# micro.net
KiCad netlist of a schematic drawn in Altium Designer
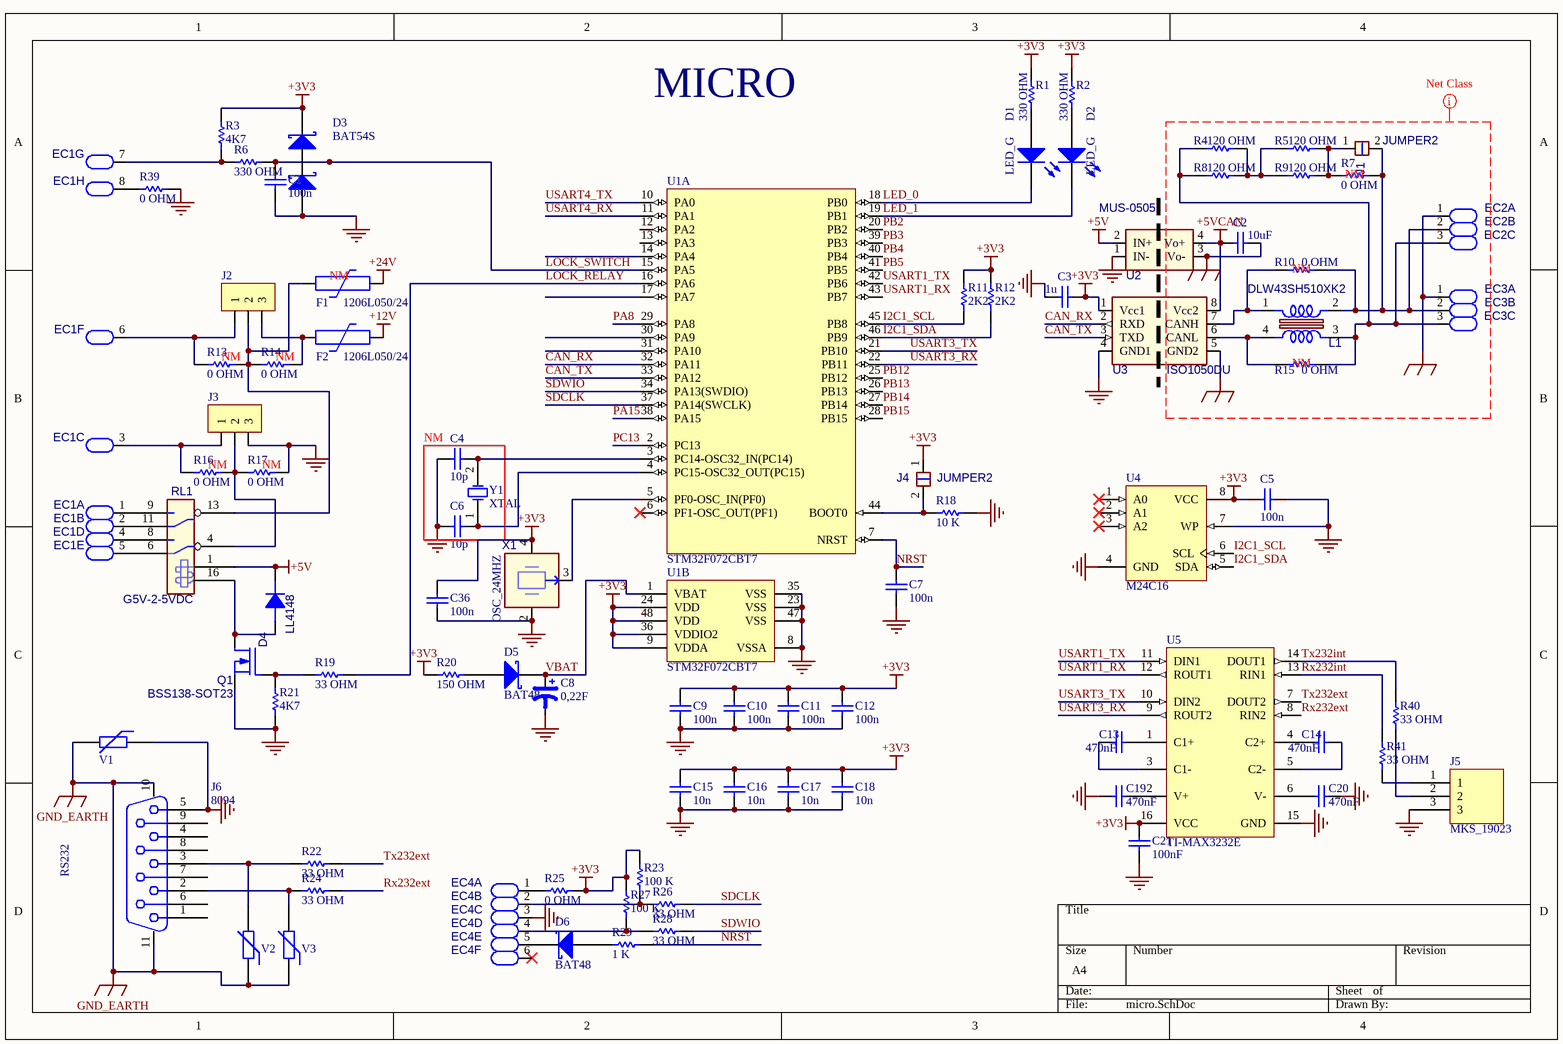
[diagram p0: micro.SchDoc]

(export (version "E")
  (design (tool "Eeschema 10.0.6"))
  (components
    (comp (ref "C1")
      (value "100n")
      (footprint "0603")
      (description "Capacitor")
      (fields (field (name "PUBLISHER") "Altium Limited"))
      (libsource (lib "sallen") (part "cond"))
    )
    (comp (ref "C2")
      (value "10uF")
      (footprint "0805")
      (description "Capacitor")
      (fields (field (name "PUBLISHER") "Altium Limited"))
      (libsource (lib "sallen") (part "cond"))
    )
    (comp (ref "C3")
      (value "1u")
      (footprint "0603")
      (description "Capacitor")
      (fields (field (name "PUBLISHER") "Altium Limited"))
      (libsource (lib "sallen") (part "cond"))
    )
    (comp (ref "C4")
      (value "10p")
      (footprint "0603")
      (description "Capacitor")
      (fields (field (name "PUBLISHER") "Altium Limited"))
      (libsource (lib "sallen") (part "cond"))
    )
    (comp (ref "C5")
      (value "100n")
      (footprint "0603")
      (description "Capacitor")
      (fields (field (name "PUBLISHER") "Altium Limited"))
      (libsource (lib "sallen") (part "cond"))
    )
    (comp (ref "C6")
      (value "10p")
      (footprint "0603")
      (description "Capacitor")
      (fields (field (name "PUBLISHER") "Altium Limited"))
      (libsource (lib "sallen") (part "cond"))
    )
    (comp (ref "C7")
      (value "100n")
      (footprint "0603")
      (description "Capacitor")
      (fields (field (name "PUBLISHER") "Altium Limited"))
      (libsource (lib "sallen") (part "cond"))
    )
    (comp (ref "C8")
      (value "0,22F")
      (footprint "EECRG0V224V")
      (description "Polarized Capacitor (Axial)")
      (fields (field (name "PUBLISHER") "Altium Limited"))
      (libsource (lib "sallen") (part "cond_pol_super"))
    )
    (comp (ref "C9")
      (value "100n")
      (footprint "0603")
      (description "Capacitor")
      (fields (field (name "PUBLISHER") "Altium Limited"))
      (libsource (lib "sallen") (part "cond"))
    )
    (comp (ref "C10")
      (value "100n")
      (footprint "0603")
      (description "Capacitor")
      (fields (field (name "PUBLISHER") "Altium Limited"))
      (libsource (lib "sallen") (part "cond"))
    )
    (comp (ref "C11")
      (value "100n")
      (footprint "0603")
      (description "Capacitor")
      (fields (field (name "PUBLISHER") "Altium Limited"))
      (libsource (lib "sallen") (part "cond"))
    )
    (comp (ref "C12")
      (value "100n")
      (footprint "0603")
      (description "Capacitor")
      (fields (field (name "PUBLISHER") "Altium Limited"))
      (libsource (lib "sallen") (part "cond"))
    )
    (comp (ref "C13")
      (value "470nF")
      (footprint "0805")
      (description "Capacitor")
      (fields (field (name "PUBLISHER") "Altium Limited"))
      (libsource (lib "sallen") (part "cond"))
    )
    (comp (ref "C14")
      (value "470nF")
      (footprint "0805")
      (description "Capacitor")
      (fields (field (name "PUBLISHER") "Altium Limited"))
      (libsource (lib "sallen") (part "cond"))
    )
    (comp (ref "C15")
      (value "10n")
      (footprint "0603")
      (description "Capacitor")
      (fields (field (name "PUBLISHER") "Altium Limited"))
      (libsource (lib "sallen") (part "cond"))
    )
    (comp (ref "C16")
      (value "10n")
      (footprint "0603")
      (description "Capacitor")
      (fields (field (name "PUBLISHER") "Altium Limited"))
      (libsource (lib "sallen") (part "cond"))
    )
    (comp (ref "C17")
      (value "10n")
      (footprint "0603")
      (description "Capacitor")
      (fields (field (name "PUBLISHER") "Altium Limited"))
      (libsource (lib "sallen") (part "cond"))
    )
    (comp (ref "C18")
      (value "10n")
      (footprint "0603")
      (description "Capacitor")
      (fields (field (name "PUBLISHER") "Altium Limited"))
      (libsource (lib "sallen") (part "cond"))
    )
    (comp (ref "C19")
      (value "470nF")
      (footprint "0805")
      (description "Capacitor")
      (fields (field (name "PUBLISHER") "Altium Limited"))
      (libsource (lib "sallen") (part "cond"))
    )
    (comp (ref "C20")
      (value "470nF")
      (footprint "0805")
      (description "Capacitor")
      (fields (field (name "PUBLISHER") "Altium Limited"))
      (libsource (lib "sallen") (part "cond"))
    )
    (comp (ref "C21")
      (value "100nF")
      (footprint "0805")
      (description "Capacitor")
      (fields (field (name "PUBLISHER") "Altium Limited"))
      (libsource (lib "sallen") (part "cond"))
    )
    (comp (ref "C36")
      (value "100n")
      (footprint "0603")
      (description "Capacitor")
      (fields (field (name "PUBLISHER") "Altium Limited"))
      (libsource (lib "sallen") (part "cond"))
    )
    (comp (ref "D1")
      (value "LED_G")
      (footprint "LED0603G")
      (description "Typical RED, GREEN, YELLOW, AMBER GaAs LED")
      (fields (field (name "PUBLISHER") "Altium Limited"))
      (libsource (lib "sallen") (part "diodo_led"))
    )
    (comp (ref "D2")
      (value "LED_G")
      (footprint "LED0603G")
      (description "Typical RED, GREEN, YELLOW, AMBER GaAs LED")
      (fields (field (name "PUBLISHER") "Altium Limited"))
      (libsource (lib "sallen") (part "diodo_led"))
    )
    (comp (ref "D3")
      (value "BAT54S")
      (footprint "SOT23")
      (description "High Current Density Surface Mount Schottky Rectifier")
      (libsource (lib "sallen") (part "BAT54S"))
    )
    (comp (ref "D4")
      (value "LL4148")
      (description "DIODE SWITCH,100V,150MA,SOD123")
      (libsource (lib "LMB_Board") (part "LL4148_(06006001)"))
    )
    (comp (ref "D5")
      (value "BAT48")
      (footprint "0805")
      (description "Schottky Diode")
      (fields (field (name "PUBLISHER") "Altium Limited"))
      (libsource (lib "sallen") (part "D Schottky"))
    )
    (comp (ref "D6")
      (value "BAT48")
      (footprint "0805")
      (description "Schottky Diode")
      (fields (field (name "PUBLISHER") "Altium Limited"))
      (libsource (lib "sallen") (part "D Schottky"))
    )
    (comp (ref "EC1")
      (value "JST_XAD_8")
      (description "Conector 8(2x4) vias (3A)")
      (libsource (lib "LMB_Board") (part "Conn_JST_XADSS_8_vias"))
    )
    (comp (ref "EC2")
      (value "Conexcon-2545-2-03-1_1")
      (description "2.54mm pitch Terminal Block 3P")
      (fields (field (name "PART NUMBER") "Conexcon-2545-2-03-1"))
      (libsource (lib "sallen") (part "Conexcon-2545-2-03-1_1"))
    )
    (comp (ref "EC3")
      (value "Conexcon-2545-2-03-1_1")
      (description "2.54mm pitch Terminal Block 3P")
      (fields (field (name "PART NUMBER") "Conexcon-2545-2-03-1"))
      (libsource (lib "sallen") (part "Conexcon-2545-2-03-1_1"))
    )
    (comp (ref "EC4")
      (value "Conexcon-2545-2-06-1")
      (description "2.54mm pitch Terminal Block 6P")
      (libsource (lib "sallen") (part "Conexcon-2545-2-06-1"))
    )
    (comp (ref "F1")
      (value "1206L050/24")
      (footprint "POLYFUSE_1206L")
      (libsource (lib "dpm_semiconductores") (part "POLYFUSE_1206L050/24"))
    )
    (comp (ref "F2")
      (value "1206L050/24")
      (footprint "POLYFUSE_1206L")
      (libsource (lib "dpm_semiconductores") (part "POLYFUSE_1206L050/24"))
    )
    (comp (ref "J1")
      (value "JUMPER2")
      (description "Jumper 2pin P=2.54mm")
      (libsource (lib "") (part "JUMPER2_1"))
    )
    (comp (ref "J2")
      (value "Header 3")
      (footprint "HDR1X3")
      (description "Header, 3-Pin")
      (fields (field (name "PUBLISHER") "Altium Limited"))
      (libsource (lib "sallen") (part "Header 3"))
    )
    (comp (ref "J3")
      (value "Header 3")
      (footprint "HDR1X3")
      (description "Header, 3-Pin")
      (fields (field (name "PUBLISHER") "Altium Limited"))
      (libsource (lib "sallen") (part "Header 3"))
    )
    (comp (ref "J4")
      (value "JUMPER2")
      (description "Jumper 2pin P=2.54mm")
      (libsource (lib "sallen") (part "JUMPER2"))
    )
    (comp (ref "J5")
      (value "MKS_19023")
      (footprint "MOLEX_MKS_19023")
      (description "Molex_MKS_19023")
      (libsource (lib "sallen") (part "MOLEX_MKS_19023"))
    )
    (comp (ref "J6") (value "8094") (footprint "8094") (libsource (lib "dpm_conectores") (part "8094")))
    (comp (ref "L1")
      (value "DLW43SH510XK2")
      (footprint "1812_DLW")
      (description "Bobina Common mode 51uH 230mA 1.0Ohm SMD 1812 /Murata")
      (libsource (lib "sallen") (part "DLW43SH510XK2"))
    )
    (comp (ref "Q1")
      (value "BSS138-SOT23")
      (description "N-Channel Logic Level Enhancement Mode Field Effect Transistor")
      (libsource (lib "LMB_Board") (part "BSS138-SOT23"))
    )
    (comp (ref "R1")
      (value "330 OHM")
      (footprint "R0603")
      (description "Resistor")
      (fields (field (name "PUBLISHER") "Altium Limited"))
      (libsource (lib "sallen") (part "res1"))
    )
    (comp (ref "R2")
      (value "330 OHM")
      (footprint "R0603")
      (description "Resistor")
      (fields (field (name "PUBLISHER") "Altium Limited"))
      (libsource (lib "sallen") (part "res1"))
    )
    (comp (ref "R3")
      (value "4K7")
      (footprint "R0603")
      (description "Resistor")
      (fields (field (name "PUBLISHER") "Altium Limited"))
      (libsource (lib "sallen") (part "res1"))
    )
    (comp (ref "R4")
      (value "120 OHM")
      (footprint "R0603")
      (description "Resistor")
      (fields (field (name "PUBLISHER") "Altium Limited"))
      (libsource (lib "sallen") (part "res1"))
    )
    (comp (ref "R5")
      (value "120 OHM")
      (footprint "R0603")
      (description "Resistor")
      (fields (field (name "PUBLISHER") "Altium Limited"))
      (libsource (lib "sallen") (part "res1"))
    )
    (comp (ref "R6")
      (value "330 OHM")
      (footprint "R0603")
      (description "Resistor")
      (fields (field (name "PUBLISHER") "Altium Limited"))
      (libsource (lib "sallen") (part "res1"))
    )
    (comp (ref "R7")
      (value "0 OHM")
      (footprint "R0603")
      (description "Resistor")
      (fields (field (name "PUBLISHER") "Altium Limited"))
      (libsource (lib "sallen") (part "res1"))
    )
    (comp (ref "R8")
      (value "120 OHM")
      (footprint "R0603")
      (description "Resistor")
      (fields (field (name "PUBLISHER") "Altium Limited"))
      (libsource (lib "sallen") (part "res1"))
    )
    (comp (ref "R9")
      (value "120 OHM")
      (footprint "R0603")
      (description "Resistor")
      (fields (field (name "PUBLISHER") "Altium Limited"))
      (libsource (lib "sallen") (part "res1"))
    )
    (comp (ref "R10")
      (value "0 OHM")
      (footprint "R0603")
      (description "Resistor")
      (fields (field (name "PUBLISHER") "Altium Limited"))
      (libsource (lib "sallen") (part "res1"))
    )
    (comp (ref "R11")
      (value "2K2")
      (footprint "R0603")
      (description "Resistor")
      (fields (field (name "PUBLISHER") "Altium Limited"))
      (libsource (lib "sallen") (part "res1"))
    )
    (comp (ref "R12")
      (value "2K2")
      (footprint "R0603")
      (description "Resistor")
      (fields (field (name "PUBLISHER") "Altium Limited"))
      (libsource (lib "sallen") (part "res1"))
    )
    (comp (ref "R13")
      (value "0 OHM")
      (footprint "R0805")
      (description "Resistor")
      (fields (field (name "PUBLISHER") "Altium Limited"))
      (libsource (lib "sallen") (part "res1"))
    )
    (comp (ref "R14")
      (value "0 OHM")
      (footprint "R0805")
      (description "Resistor")
      (fields (field (name "PUBLISHER") "Altium Limited"))
      (libsource (lib "sallen") (part "res1"))
    )
    (comp (ref "R15")
      (value "0 OHM")
      (footprint "R0603")
      (description "Resistor")
      (fields (field (name "PUBLISHER") "Altium Limited"))
      (libsource (lib "sallen") (part "res1"))
    )
    (comp (ref "R16")
      (value "0 OHM")
      (footprint "R0805")
      (description "Resistor")
      (fields (field (name "PUBLISHER") "Altium Limited"))
      (libsource (lib "sallen") (part "res1"))
    )
    (comp (ref "R17")
      (value "0 OHM")
      (footprint "R0805")
      (description "Resistor")
      (fields (field (name "PUBLISHER") "Altium Limited"))
      (libsource (lib "sallen") (part "res1"))
    )
    (comp (ref "R18")
      (value "10 K")
      (footprint "R0603")
      (description "Resistor")
      (fields (field (name "PUBLISHER") "Altium Limited"))
      (libsource (lib "sallen") (part "res1"))
    )
    (comp (ref "R19")
      (value "33 OHM")
      (footprint "R0603")
      (description "Resistor")
      (fields (field (name "PUBLISHER") "Altium Limited"))
      (libsource (lib "sallen") (part "res1"))
    )
    (comp (ref "R20")
      (value "150 OHM")
      (footprint "R0603")
      (description "Resistor")
      (fields (field (name "PUBLISHER") "Altium Limited"))
      (libsource (lib "sallen") (part "res1"))
    )
    (comp (ref "R21")
      (value "4K7")
      (footprint "R0603")
      (description "Resistor")
      (fields (field (name "PUBLISHER") "Altium Limited"))
      (libsource (lib "sallen") (part "res1"))
    )
    (comp (ref "R22")
      (value "33 OHM")
      (footprint "R0603")
      (description "Resistor")
      (fields (field (name "PUBLISHER") "Altium Limited"))
      (libsource (lib "sallen") (part "res1"))
    )
    (comp (ref "R23")
      (value "100 K")
      (footprint "R0603")
      (description "Resistor")
      (fields (field (name "PUBLISHER") "Altium Limited"))
      (libsource (lib "sallen") (part "res1"))
    )
    (comp (ref "R24")
      (value "33 OHM")
      (footprint "R0603")
      (description "Resistor")
      (fields (field (name "PUBLISHER") "Altium Limited"))
      (libsource (lib "sallen") (part "res1"))
    )
    (comp (ref "R25")
      (value "0 OHM")
      (footprint "R0603")
      (description "Resistor")
      (fields (field (name "PUBLISHER") "Altium Limited"))
      (libsource (lib "sallen") (part "res1"))
    )
    (comp (ref "R26")
      (value "33 OHM")
      (footprint "R0603")
      (description "Resistor")
      (fields (field (name "PUBLISHER") "Altium Limited"))
      (libsource (lib "sallen") (part "res1"))
    )
    (comp (ref "R27")
      (value "100 K")
      (footprint "R0603")
      (description "Resistor")
      (fields (field (name "PUBLISHER") "Altium Limited"))
      (libsource (lib "sallen") (part "res1"))
    )
    (comp (ref "R28")
      (value "33 OHM")
      (footprint "R0603")
      (description "Resistor")
      (fields (field (name "PUBLISHER") "Altium Limited"))
      (libsource (lib "sallen") (part "res1"))
    )
    (comp (ref "R29")
      (value "1 K")
      (footprint "R0603")
      (description "Resistor")
      (fields (field (name "PUBLISHER") "Altium Limited"))
      (libsource (lib "sallen") (part "res1"))
    )
    (comp (ref "R39")
      (value "0 OHM")
      (footprint "R0603")
      (description "Resistor")
      (fields (field (name "PUBLISHER") "Altium Limited"))
      (libsource (lib "sallen") (part "res1"))
    )
    (comp (ref "R40")
      (value "33 OHM")
      (footprint "R0603")
      (description "Resistor")
      (fields (field (name "PUBLISHER") "Altium Limited"))
      (libsource (lib "sallen") (part "res1"))
    )
    (comp (ref "R41")
      (value "33 OHM")
      (footprint "R0603")
      (description "Resistor")
      (fields (field (name "PUBLISHER") "Altium Limited"))
      (libsource (lib "sallen") (part "res1"))
    )
    (comp (ref "RL1")
      (value "G5V-2-5VDC")
      (footprint "RL-OMRON-G5V-2-5VDC")
      (description "Omrom Relay G5V-2-5VDC")
      (libsource (lib "LMB_Board") (part "G5V-2-5VDC"))
    )
    (comp (ref "U1")
      (value "STM32F072CBT7")
      (footprint "STM-LQFP48_N_3d")
      (libsource (lib "sallen") (part "STM32F072CBT7"))
    )
    (comp (ref "U2")
      (value "MUS-0505")
      (description "Convertidor DC/DC isolated 1W 5v/5v 1.8E DANUBE (eQ XpPower IE0505S)")
      (libsource (lib "sallen") (part "MUS-0505"))
    )
    (comp (ref "U3")
      (value "ISO1050DU")
      (description "CAN Transceiver Isolated 3-5vcc (-55º-105ºC)SOP8-DIP")
      (libsource (lib "sallen") (part "ISO1050DU"))
    )
    (comp (ref "U4")
      (value "M24C16")
      (footprint "SO08")
      (libsource (lib "sallen") (part "MEM-SEEPROM-AT24C-IL8"))
    )
    (comp (ref "U5")
      (value "TI-MAX3232E")
      (footprint "SOIC16")
      (libsource (lib "sallen") (part "TI-MAX3232E"))
    )
    (comp (ref "V1")
      (value "VC080526C580")
      (footprint "VC080526C580")
      (description "Varistor (Voltage-Sensitive Resistor)")
      (libsource (lib "dpm_pasivos") (part "VC080526C580"))
    )
    (comp (ref "V2")
      (value "VC080526C580")
      (footprint "VC080526C580")
      (description "Varistor (Voltage-Sensitive Resistor)")
      (libsource (lib "dpm_pasivos") (part "VC080526C580"))
    )
    (comp (ref "V3")
      (value "VC080526C580")
      (footprint "VC080526C580")
      (description "Varistor (Voltage-Sensitive Resistor)")
      (libsource (lib "dpm_pasivos") (part "VC080526C580"))
    )
    (comp (ref "X1")
      (value "OSC_24MHZ")
      (description "Oscillator 7x5mm 24Mhz 3.3v 4p s73305T-24 //Aker-usa")
      (libsource (lib "LMB_Board") (part "OSC7X5_4P3.3-24MHZ"))
    )
    (comp (ref "Y1")
      (value "XTAL")
      (footprint "R38")
      (description "Crystal Oscillator")
      (fields (field (name "PUBLISHER") "Altium Limited"))
      (libsource (lib "Miscellaneous Devices") (part "XTAL"))
    )
  )
  (nets
    (net (code "1") (name "+3V3") (class "Default")
      (node (ref "C10") (pin "2") (pinfunction "2_2") (pintype "passive"))
      (node (ref "C11") (pin "2") (pinfunction "2_2") (pintype "passive"))
      (node (ref "C12") (pin "2") (pinfunction "2_2") (pintype "passive"))
      (node (ref "C15") (pin "2") (pinfunction "2_2") (pintype "passive"))
      (node (ref "C16") (pin "2") (pinfunction "2_2") (pintype "passive"))
      (node (ref "C17") (pin "2") (pinfunction "2_2") (pintype "passive"))
      (node (ref "C18") (pin "2") (pinfunction "2_2") (pintype "passive"))
      (node (ref "C21") (pin "1") (pinfunction "1_1") (pintype "passive"))
      (node (ref "C3") (pin "1") (pinfunction "1_1") (pintype "passive"))
      (node (ref "C36") (pin "2") (pinfunction "2_2") (pintype "passive"))
      (node (ref "C5") (pin "2") (pinfunction "2_2") (pintype "passive"))
      (node (ref "C9") (pin "2") (pinfunction "2_2") (pintype "passive"))
      (node (ref "D3") (pin "2") (pinfunction "K_2") (pintype "passive"))
      (node (ref "J4") (pin "1") (pinfunction "1_1") (pintype "passive"))
      (node (ref "R1") (pin "2") (pinfunction "2_2") (pintype "passive"))
      (node (ref "R11") (pin "1") (pinfunction "1_1") (pintype "passive"))
      (node (ref "R12") (pin "1") (pinfunction "1_1") (pintype "passive"))
      (node (ref "R2") (pin "2") (pinfunction "2_2") (pintype "passive"))
      (node (ref "R20") (pin "1") (pinfunction "1_1") (pintype "passive"))
      (node (ref "R23") (pin "2") (pinfunction "2_2") (pintype "passive"))
      (node (ref "R25") (pin "1") (pinfunction "1_1") (pintype "passive"))
      (node (ref "R27") (pin "2") (pinfunction "2_2") (pintype "passive"))
      (node (ref "R3") (pin "2") (pinfunction "2_2") (pintype "passive"))
      (node (ref "U1") (pin "24") (pinfunction "VDD_24") (pintype "power_in"))
      (node (ref "U1") (pin "36") (pinfunction "VDDIO2_36") (pintype "power_in"))
      (node (ref "U1") (pin "48") (pinfunction "VDD_48") (pintype "power_in"))
      (node (ref "U1") (pin "9") (pinfunction "VDDA_9") (pintype "power_in"))
      (node (ref "U3") (pin "1") (pinfunction "Vcc1_1") (pintype "power_in"))
      (node (ref "U4") (pin "8") (pinfunction "VCC_8") (pintype "power_in"))
      (node (ref "U5") (pin "16") (pinfunction "VCC_16") (pintype "power_in"))
      (node (ref "X1") (pin "4") (pinfunction "4_4") (pintype "passive"))
    )
    (net (code "2") (name "+5V") (class "Default")
      (node (ref "D4") (pin "2") (pinfunction "K_2") (pintype "passive"))
      (node (ref "RL1") (pin "1") (pinfunction "COIL1_1") (pintype "passive"))
      (node (ref "U2") (pin "2") (pinfunction "IN+_2") (pintype "power_in"))
    )
    (net (code "3") (name "+5VCAN") (class "Default")
      (node (ref "C2") (pin "1") (pinfunction "1_1") (pintype "passive"))
      (node (ref "U2") (pin "4") (pinfunction "Vo+_4") (pintype "power_in"))
      (node (ref "U3") (pin "8") (pinfunction "Vcc2_8") (pintype "power_in"))
    )
    (net (code "4") (name "+12V") (class "Default")
      (node (ref "F2") (pin "2") (pinfunction "2_2") (pintype "passive"))
    )
    (net (code "5") (name "+24V") (class "Default")
      (node (ref "F1") (pin "2") (pinfunction "2_2") (pintype "passive"))
    )
    (net (code "6") (name "/CAN_RX") (class "Default")
      (node (ref "U1") (pin "32") (pinfunction "PA11_32") (pintype "bidirectional"))
      (node (ref "U3") (pin "2") (pinfunction "RXD_2") (pintype "output"))
    )
    (net (code "7") (name "/CAN_TX") (class "Default")
      (node (ref "U1") (pin "33") (pinfunction "PA12_33") (pintype "bidirectional"))
      (node (ref "U3") (pin "3") (pinfunction "TXD_3") (pintype "input"))
    )
    (net (code "8") (name "/I2C1_SCL") (class "Default")
      (node (ref "R11") (pin "2") (pinfunction "2_2") (pintype "passive"))
      (node (ref "U1") (pin "45") (pinfunction "PB8_45") (pintype "bidirectional"))
      (node (ref "U4") (pin "6") (pinfunction "SCL_6") (pintype "input"))
    )
    (net (code "9") (name "/I2C1_SDA") (class "Default")
      (node (ref "R12") (pin "2") (pinfunction "2_2") (pintype "passive"))
      (node (ref "U1") (pin "46") (pinfunction "PB9_46") (pintype "bidirectional"))
      (node (ref "U4") (pin "5") (pinfunction "SDA_5") (pintype "bidirectional"))
    )
    (net (code "10") (name "/LED_0") (class "Default")
      (node (ref "D1") (pin "2") (pinfunction "K_2") (pintype "passive"))
      (node (ref "U1") (pin "18") (pinfunction "PB0_18") (pintype "bidirectional"))
    )
    (net (code "11") (name "/LED_1") (class "Default")
      (node (ref "D2") (pin "2") (pinfunction "K_2") (pintype "passive"))
      (node (ref "U1") (pin "19") (pinfunction "PB1_19") (pintype "bidirectional"))
    )
    (net (code "12") (name "/LOCK_RELAY") (class "Default")
      (node (ref "R19") (pin "2") (pinfunction "2_2") (pintype "passive"))
      (node (ref "U1") (pin "16") (pinfunction "PA6_16") (pintype "bidirectional"))
    )
    (net (code "13") (name "/LOCK_SWITCH") (class "Default")
      (node (ref "C1") (pin "2") (pinfunction "2_2") (pintype "passive"))
      (node (ref "D3") (pin "3") (pinfunction "KA_3") (pintype "passive"))
      (node (ref "R6") (pin "1") (pinfunction "1_1") (pintype "passive"))
      (node (ref "U1") (pin "15") (pinfunction "PA5_15") (pintype "bidirectional"))
    )
    (net (code "14") (name "/NRST") (class "Default")
      (node (ref "C7") (pin "2") (pinfunction "2_2") (pintype "passive"))
      (node (ref "R29") (pin "2") (pinfunction "2_2") (pintype "passive"))
      (node (ref "U1") (pin "7") (pinfunction "NRST_7") (pintype "bidirectional"))
    )
    (net (code "15") (name "/PA8") (class "Default")
      (node (ref "U1") (pin "29") (pinfunction "PA8_29") (pintype "bidirectional"))
    )
    (net (code "16") (name "/PA15") (class "Default")
      (node (ref "U1") (pin "38") (pinfunction "PA15_38") (pintype "bidirectional"))
    )
    (net (code "17") (name "/PB2") (class "Default")
      (node (ref "U1") (pin "20") (pinfunction "PB2_20") (pintype "bidirectional"))
    )
    (net (code "18") (name "/PB3") (class "Default")
      (node (ref "U1") (pin "39") (pinfunction "PB3_39") (pintype "bidirectional"))
    )
    (net (code "19") (name "/PB4") (class "Default")
      (node (ref "U1") (pin "40") (pinfunction "PB4_40") (pintype "bidirectional"))
    )
    (net (code "20") (name "/PB5") (class "Default")
      (node (ref "U1") (pin "41") (pinfunction "PB5_41") (pintype "bidirectional"))
    )
    (net (code "21") (name "/PB12") (class "Default")
      (node (ref "U1") (pin "25") (pinfunction "PB12_25") (pintype "bidirectional"))
    )
    (net (code "22") (name "/PB13") (class "Default")
      (node (ref "U1") (pin "26") (pinfunction "PB13_26") (pintype "bidirectional"))
    )
    (net (code "23") (name "/PB14") (class "Default")
      (node (ref "U1") (pin "27") (pinfunction "PB14_27") (pintype "bidirectional"))
    )
    (net (code "24") (name "/PB15") (class "Default")
      (node (ref "U1") (pin "28") (pinfunction "PB15_28") (pintype "bidirectional"))
    )
    (net (code "25") (name "/PC13") (class "Default")
      (node (ref "U1") (pin "2") (pinfunction "PC13_2") (pintype "bidirectional"))
    )
    (net (code "26") (name "/Rx232ext") (class "Default")
      (node (ref "R24") (pin "2") (pinfunction "2_2") (pintype "passive"))
      (node (ref "U5") (pin "8") (pinfunction "RIN2_8") (pintype "input"))
    )
    (net (code "27") (name "/Rx232int") (class "Default")
      (node (ref "R41") (pin "2") (pinfunction "2_2") (pintype "passive"))
      (node (ref "U5") (pin "13") (pinfunction "RIN1_13") (pintype "input"))
    )
    (net (code "28") (name "/SDCLK") (class "Default")
      (node (ref "R26") (pin "2") (pinfunction "2_2") (pintype "passive"))
      (node (ref "U1") (pin "37") (pinfunction "PA14(SWCLK)_37") (pintype "bidirectional"))
    )
    (net (code "29") (name "/SDWIO") (class "Default")
      (node (ref "R28") (pin "2") (pinfunction "2_2") (pintype "passive"))
      (node (ref "U1") (pin "34") (pinfunction "PA13(SWDIO)_34") (pintype "bidirectional"))
    )
    (net (code "30") (name "/Tx232ext") (class "Default")
      (node (ref "R22") (pin "2") (pinfunction "2_2") (pintype "passive"))
      (node (ref "U5") (pin "7") (pinfunction "DOUT2_7") (pintype "output"))
    )
    (net (code "31") (name "/Tx232int") (class "Default")
      (node (ref "R40") (pin "2") (pinfunction "2_2") (pintype "passive"))
      (node (ref "U5") (pin "14") (pinfunction "DOUT1_14") (pintype "output"))
    )
    (net (code "32") (name "/USART1_RX") (class "Default")
      (node (ref "U1") (pin "43") (pinfunction "PB7_43") (pintype "bidirectional"))
      (node (ref "U5") (pin "12") (pinfunction "ROUT1_12") (pintype "output"))
    )
    (net (code "33") (name "/USART1_TX") (class "Default")
      (node (ref "U1") (pin "42") (pinfunction "PB6_42") (pintype "bidirectional"))
      (node (ref "U5") (pin "11") (pinfunction "DIN1_11") (pintype "input"))
    )
    (net (code "34") (name "/USART3_RX") (class "Default")
      (node (ref "U1") (pin "22") (pinfunction "PB11_22") (pintype "bidirectional"))
      (node (ref "U5") (pin "9") (pinfunction "ROUT2_9") (pintype "output"))
    )
    (net (code "35") (name "/USART3_TX") (class "Default")
      (node (ref "U1") (pin "21") (pinfunction "PB10_21") (pintype "bidirectional"))
      (node (ref "U5") (pin "10") (pinfunction "DIN2_10") (pintype "input"))
    )
    (net (code "36") (name "/USART4_RX") (class "Default")
      (node (ref "U1") (pin "11") (pinfunction "PA1_11") (pintype "bidirectional"))
    )
    (net (code "37") (name "/USART4_TX") (class "Default")
      (node (ref "U1") (pin "10") (pinfunction "PA0_10") (pintype "bidirectional"))
    )
    (net (code "38") (name "/VBAT") (class "Default")
      (node (ref "C8") (pin "1") (pinfunction "1_1") (pintype "passive"))
      (node (ref "D5") (pin "2") (pinfunction "K_2") (pintype "passive"))
      (node (ref "U1") (pin "1") (pinfunction "VBAT_1") (pintype "power_in"))
    )
    (net (code "39") (name "GND") (class "Default")
      (node (ref "C1") (pin "1") (pinfunction "1_1") (pintype "passive"))
      (node (ref "C10") (pin "1") (pinfunction "1_1") (pintype "passive"))
      (node (ref "C11") (pin "1") (pinfunction "1_1") (pintype "passive"))
      (node (ref "C12") (pin "1") (pinfunction "1_1") (pintype "passive"))
      (node (ref "C15") (pin "1") (pinfunction "1_1") (pintype "passive"))
      (node (ref "C16") (pin "1") (pinfunction "1_1") (pintype "passive"))
      (node (ref "C17") (pin "1") (pinfunction "1_1") (pintype "passive"))
      (node (ref "C18") (pin "1") (pinfunction "1_1") (pintype "passive"))
      (node (ref "C19") (pin "1") (pinfunction "1_1") (pintype "passive"))
      (node (ref "C20") (pin "2") (pinfunction "2_2") (pintype "passive"))
      (node (ref "C21") (pin "2") (pinfunction "2_2") (pintype "passive"))
      (node (ref "C3") (pin "2") (pinfunction "2_2") (pintype "passive"))
      (node (ref "C36") (pin "1") (pinfunction "1_1") (pintype "passive"))
      (node (ref "C4") (pin "1") (pinfunction "1_1") (pintype "passive"))
      (node (ref "C5") (pin "1") (pinfunction "1_1") (pintype "passive"))
      (node (ref "C6") (pin "1") (pinfunction "1_1") (pintype "passive"))
      (node (ref "C7") (pin "1") (pinfunction "1_1") (pintype "passive"))
      (node (ref "C8") (pin "2") (pinfunction "2_2") (pintype "passive"))
      (node (ref "C9") (pin "1") (pinfunction "1_1") (pintype "passive"))
      (node (ref "D3") (pin "1") (pinfunction "A_1") (pintype "passive"))
      (node (ref "EC4") (pin "3") (pinfunction "3_3") (pintype "passive"))
      (node (ref "J3") (pin "3") (pinfunction "3_3") (pintype "passive"))
      (node (ref "J5") (pin "3") (pinfunction "3_3") (pintype "passive"))
      (node (ref "J6") (pin "5") (pinfunction "5_5") (pintype "passive"))
      (node (ref "Q1") (pin "S") (pinfunction "S_S") (pintype "passive"))
      (node (ref "R17") (pin "1") (pinfunction "1_1") (pintype "passive"))
      (node (ref "R18") (pin "1") (pinfunction "1_1") (pintype "passive"))
      (node (ref "R21") (pin "1") (pinfunction "1_1") (pintype "passive"))
      (node (ref "R39") (pin "1") (pinfunction "1_1") (pintype "passive"))
      (node (ref "U1") (pin "23") (pinfunction "VSS_23") (pintype "power_in"))
      (node (ref "U1") (pin "35") (pinfunction "VSS_35") (pintype "power_in"))
      (node (ref "U1") (pin "47") (pinfunction "VSS_47") (pintype "power_in"))
      (node (ref "U1") (pin "8") (pinfunction "VSSA_8") (pintype "power_in"))
      (node (ref "U2") (pin "1") (pinfunction "IN-_1") (pintype "power_in"))
      (node (ref "U3") (pin "4") (pinfunction "GND1_4") (pintype "power_in"))
      (node (ref "U4") (pin "4") (pinfunction "GND_4") (pintype "power_in"))
      (node (ref "U4") (pin "7") (pinfunction "WP_7") (pintype "input"))
      (node (ref "U5") (pin "15") (pinfunction "GND_15") (pintype "power_in"))
      (node (ref "V1") (pin "1") (pinfunction "1_1") (pintype "passive"))
      (node (ref "X1") (pin "2") (pinfunction "2_2") (pintype "passive"))
    )
    (net (code "40") (name "GND_CAN") (class "Default")
      (node (ref "C2") (pin "2") (pinfunction "2_2") (pintype "passive"))
      (node (ref "EC2") (pin "1") (pinfunction "1_1") (pintype "passive"))
      (node (ref "EC3") (pin "1") (pinfunction "1_1") (pintype "passive"))
      (node (ref "U2") (pin "3") (pinfunction "Vo-_3") (pintype "power_in"))
      (node (ref "U3") (pin "5") (pinfunction "GND2_5") (pintype "power_in"))
    )
    (net (code "41") (name "GND_EARTH") (class "Default")
      (node (ref "J6") (pin "10") (pinfunction "10_10") (pintype "passive"))
      (node (ref "J6") (pin "11") (pinfunction "11_11") (pintype "passive"))
      (node (ref "V1") (pin "2") (pinfunction "2_2") (pintype "passive"))
      (node (ref "V2") (pin "1") (pinfunction "1_1") (pintype "passive"))
      (node (ref "V3") (pin "1") (pinfunction "1_1") (pintype "passive"))
    )
    (net (code "42") (name "Net-(D1-A)") (class "Default")
      (node (ref "D1") (pin "1") (pinfunction "A_1") (pintype "passive"))
      (node (ref "R1") (pin "1") (pinfunction "1_1") (pintype "passive"))
    )
    (net (code "43") (name "Net-(D2-A)") (class "Default")
      (node (ref "D2") (pin "1") (pinfunction "A_1") (pintype "passive"))
      (node (ref "R2") (pin "1") (pinfunction "1_1") (pintype "passive"))
    )
    (net (code "44") (name "Net-(D4-A)") (class "Default")
      (node (ref "D4") (pin "1") (pinfunction "A_1") (pintype "passive"))
      (node (ref "Q1") (pin "D") (pinfunction "D_D") (pintype "passive"))
      (node (ref "RL1") (pin "16") (pinfunction "COIL2_16") (pintype "passive"))
    )
    (net (code "45") (name "Net-(D5-A)") (class "Default")
      (node (ref "D5") (pin "1") (pinfunction "A_1") (pintype "passive"))
      (node (ref "R20") (pin "2") (pinfunction "2_2") (pintype "passive"))
    )
    (net (code "46") (name "Net-(D6-A)") (class "Default")
      (node (ref "D6") (pin "1") (pinfunction "A_1") (pintype "passive"))
      (node (ref "R29") (pin "1") (pinfunction "1_1") (pintype "passive"))
    )
    (net (code "47") (name "Net-(D6-K)") (class "Default")
      (node (ref "D6") (pin "2") (pinfunction "K_2") (pintype "passive"))
      (node (ref "EC4") (pin "5") (pinfunction "5_5") (pintype "passive"))
    )
    (net (code "48") (name "Net-(EC1-Pad1)") (class "Default")
      (node (ref "EC1") (pin "1") (pinfunction "1_1") (pintype "passive"))
      (node (ref "RL1") (pin "9") (pinfunction "NO_9") (pintype "passive"))
    )
    (net (code "49") (name "Net-(EC1-Pad2)") (class "Default")
      (node (ref "EC1") (pin "2") (pinfunction "2_2") (pintype "passive"))
      (node (ref "RL1") (pin "11") (pinfunction "NO_11") (pintype "passive"))
    )
    (net (code "50") (name "Net-(EC1-Pad3)") (class "Default")
      (node (ref "EC1") (pin "3") (pinfunction "3_3") (pintype "passive"))
      (node (ref "J3") (pin "1") (pinfunction "1_1") (pintype "passive"))
      (node (ref "R16") (pin "2") (pinfunction "2_2") (pintype "passive"))
    )
    (net (code "51") (name "Net-(EC1-Pad4)") (class "Default")
      (node (ref "EC1") (pin "4") (pinfunction "4_4") (pintype "passive"))
      (node (ref "RL1") (pin "8") (pinfunction "NO_8") (pintype "passive"))
    )
    (net (code "52") (name "Net-(EC1-Pad5)") (class "Default")
      (node (ref "EC1") (pin "5") (pinfunction "5_5") (pintype "passive"))
      (node (ref "RL1") (pin "6") (pinfunction "NO_6") (pintype "passive"))
    )
    (net (code "53") (name "Net-(EC1-Pad6)") (class "Default")
      (node (ref "EC1") (pin "6") (pinfunction "6_6") (pintype "passive"))
      (node (ref "J2") (pin "1") (pinfunction "1_1") (pintype "passive"))
      (node (ref "R13") (pin "2") (pinfunction "2_2") (pintype "passive"))
    )
    (net (code "54") (name "Net-(EC1-Pad7)") (class "Default")
      (node (ref "EC1") (pin "7") (pinfunction "7_7") (pintype "passive"))
      (node (ref "R3") (pin "1") (pinfunction "1_1") (pintype "passive"))
      (node (ref "R6") (pin "2") (pinfunction "2_2") (pintype "passive"))
    )
    (net (code "55") (name "Net-(EC1-Pad8)") (class "Default")
      (node (ref "EC1") (pin "8") (pinfunction "8_8") (pintype "passive"))
      (node (ref "R39") (pin "2") (pinfunction "2_2") (pintype "passive"))
    )
    (net (code "56") (name "Net-(EC2-Pad2)") (class "Default")
      (node (ref "EC2") (pin "2") (pinfunction "2_2") (pintype "passive"))
      (node (ref "EC3") (pin "2") (pinfunction "2_2") (pintype "passive"))
      (node (ref "J1") (pin "2") (pinfunction "2_2") (pintype "passive"))
      (node (ref "L1") (pin "2") (pinfunction "2_2") (pintype "passive"))
      (node (ref "R10") (pin "2") (pinfunction "2_2") (pintype "passive"))
      (node (ref "R7") (pin "2") (pinfunction "2_2") (pintype "passive"))
    )
    (net (code "57") (name "Net-(EC2-Pad3)") (class "Default")
      (node (ref "EC2") (pin "3") (pinfunction "3_3") (pintype "passive"))
      (node (ref "EC3") (pin "3") (pinfunction "3_3") (pintype "passive"))
      (node (ref "L1") (pin "3") (pinfunction "3_3") (pintype "passive"))
      (node (ref "R15") (pin "2") (pinfunction "2_2") (pintype "passive"))
      (node (ref "R4") (pin "1") (pinfunction "1_1") (pintype "passive"))
      (node (ref "R8") (pin "1") (pinfunction "1_1") (pintype "passive"))
    )
    (net (code "58") (name "Net-(EC4-Pad1)") (class "Default")
      (node (ref "EC4") (pin "1") (pinfunction "1_1") (pintype "passive"))
      (node (ref "R25") (pin "2") (pinfunction "2_2") (pintype "passive"))
    )
    (net (code "59") (name "Net-(EC4-Pad2)") (class "Default")
      (node (ref "EC4") (pin "2") (pinfunction "2_2") (pintype "passive"))
      (node (ref "R23") (pin "1") (pinfunction "1_1") (pintype "passive"))
      (node (ref "R26") (pin "1") (pinfunction "1_1") (pintype "passive"))
    )
    (net (code "60") (name "Net-(EC4-Pad4)") (class "Default")
      (node (ref "EC4") (pin "4") (pinfunction "4_4") (pintype "passive"))
      (node (ref "R27") (pin "1") (pinfunction "1_1") (pintype "passive"))
      (node (ref "R28") (pin "1") (pinfunction "1_1") (pintype "passive"))
    )
    (net (code "61") (name "Net-(F1-Pad1)") (class "Default")
      (node (ref "F1") (pin "1") (pinfunction "1_1") (pintype "passive"))
      (node (ref "J2") (pin "2") (pinfunction "2_2") (pintype "passive"))
      (node (ref "R13") (pin "1") (pinfunction "1_1") (pintype "passive"))
      (node (ref "R14") (pin "2") (pinfunction "2_2") (pintype "passive"))
      (node (ref "RL1") (pin "13") (pinfunction "COMMON_13") (pintype "passive"))
    )
    (net (code "62") (name "Net-(F2-Pad1)") (class "Default")
      (node (ref "F2") (pin "1") (pinfunction "1_1") (pintype "passive"))
      (node (ref "J2") (pin "3") (pinfunction "3_3") (pintype "passive"))
      (node (ref "R14") (pin "1") (pinfunction "1_1") (pintype "passive"))
    )
    (net (code "63") (name "Net-(J1-Pad1)") (class "Default")
      (node (ref "J1") (pin "1") (pinfunction "1_1") (pintype "passive"))
      (node (ref "R5") (pin "2") (pinfunction "2_2") (pintype "passive"))
      (node (ref "R7") (pin "1") (pinfunction "1_1") (pintype "passive"))
      (node (ref "R9") (pin "2") (pinfunction "2_2") (pintype "passive"))
    )
    (net (code "64") (name "Net-(J3-Pad2)") (class "Default")
      (node (ref "J3") (pin "2") (pinfunction "2_2") (pintype "passive"))
      (node (ref "R16") (pin "1") (pinfunction "1_1") (pintype "passive"))
      (node (ref "R17") (pin "2") (pinfunction "2_2") (pintype "passive"))
      (node (ref "RL1") (pin "4") (pinfunction "COMMON_4") (pintype "passive"))
    )
    (net (code "65") (name "Net-(J5-Pad1)") (class "Default")
      (node (ref "J5") (pin "1") (pinfunction "1_1") (pintype "passive"))
      (node (ref "R41") (pin "1") (pinfunction "1_1") (pintype "passive"))
    )
    (net (code "66") (name "Net-(J5-Pad2)") (class "Default")
      (node (ref "J5") (pin "2") (pinfunction "2_2") (pintype "passive"))
      (node (ref "R40") (pin "1") (pinfunction "1_1") (pintype "passive"))
    )
    (net (code "67") (name "Net-(J6-Pad2)") (class "Default")
      (node (ref "J6") (pin "2") (pinfunction "2_2") (pintype "passive"))
      (node (ref "R24") (pin "1") (pinfunction "1_1") (pintype "passive"))
      (node (ref "V3") (pin "2") (pinfunction "2_2") (pintype "passive"))
    )
    (net (code "68") (name "Net-(J6-Pad3)") (class "Default")
      (node (ref "J6") (pin "3") (pinfunction "3_3") (pintype "passive"))
      (node (ref "R22") (pin "1") (pinfunction "1_1") (pintype "passive"))
      (node (ref "V2") (pin "2") (pinfunction "2_2") (pintype "passive"))
    )
    (net (code "69") (name "Net-(Q1-PadG)") (class "Default")
      (node (ref "Q1") (pin "G") (pinfunction "G_G") (pintype "passive"))
      (node (ref "R19") (pin "1") (pinfunction "1_1") (pintype "passive"))
      (node (ref "R21") (pin "2") (pinfunction "2_2") (pintype "passive"))
    )
    (net (code "70") (name "Net-(R4-Pad2)") (class "Default")
      (node (ref "R4") (pin "2") (pinfunction "2_2") (pintype "passive"))
      (node (ref "R5") (pin "1") (pinfunction "1_1") (pintype "passive"))
      (node (ref "R8") (pin "2") (pinfunction "2_2") (pintype "passive"))
      (node (ref "R9") (pin "1") (pinfunction "1_1") (pintype "passive"))
    )
    (net (code "71") (name "Net-(U1A-BOOT0)") (class "Default")
      (node (ref "J4") (pin "2") (pinfunction "2_2") (pintype "passive"))
      (node (ref "R18") (pin "2") (pinfunction "2_2") (pintype "passive"))
      (node (ref "U1") (pin "44") (pinfunction "BOOT0_44") (pintype "input"))
    )
    (net (code "72") (name "Net-(U1A-PC14-OSC32_IN(PC14))") (class "Default")
      (node (ref "C4") (pin "2") (pinfunction "2_2") (pintype "passive"))
      (node (ref "U1") (pin "3") (pinfunction "PC14-OSC32_IN(PC14)_3") (pintype "bidirectional"))
      (node (ref "Y1") (pin "2") (pinfunction "OSC2_2") (pintype "passive"))
    )
    (net (code "73") (name "Net-(U1A-PC15-OSC32_OUT(PC15))") (class "Default")
      (node (ref "C6") (pin "2") (pinfunction "2_2") (pintype "passive"))
      (node (ref "U1") (pin "4") (pinfunction "PC15-OSC32_OUT(PC15)_4") (pintype "bidirectional"))
      (node (ref "Y1") (pin "1") (pinfunction "OSC1_1") (pintype "passive"))
    )
    (net (code "74") (name "Net-(U1A-PF0-OSC_IN(PF0))") (class "Default")
      (node (ref "U1") (pin "5") (pinfunction "PF0-OSC_IN(PF0)_5") (pintype "bidirectional"))
      (node (ref "X1") (pin "3") (pinfunction "3_3") (pintype "passive"))
    )
    (net (code "75") (name "Net-(U3-CANH)") (class "Default")
      (node (ref "L1") (pin "1") (pinfunction "1_1") (pintype "passive"))
      (node (ref "R10") (pin "1") (pinfunction "1_1") (pintype "passive"))
      (node (ref "U3") (pin "7") (pinfunction "CANH_7") (pintype "bidirectional"))
    )
    (net (code "76") (name "Net-(U3-CANL)") (class "Default")
      (node (ref "L1") (pin "4") (pinfunction "4_4") (pintype "passive"))
      (node (ref "R15") (pin "1") (pinfunction "1_1") (pintype "passive"))
      (node (ref "U3") (pin "6") (pinfunction "CANL_6") (pintype "bidirectional"))
    )
    (net (code "77") (name "Net-(U5-C1+)") (class "Default")
      (node (ref "C13") (pin "2") (pinfunction "2_2") (pintype "passive"))
      (node (ref "U5") (pin "1") (pinfunction "C1+_1") (pintype "passive"))
    )
    (net (code "78") (name "Net-(U5-C1-)") (class "Default")
      (node (ref "C13") (pin "1") (pinfunction "1_1") (pintype "passive"))
      (node (ref "U5") (pin "3") (pinfunction "C1-_3") (pintype "passive"))
    )
    (net (code "79") (name "Net-(U5-C2+)") (class "Default")
      (node (ref "C14") (pin "1") (pinfunction "1_1") (pintype "passive"))
      (node (ref "U5") (pin "4") (pinfunction "C2+_4") (pintype "passive"))
    )
    (net (code "80") (name "Net-(U5-C2-)") (class "Default")
      (node (ref "C14") (pin "2") (pinfunction "2_2") (pintype "passive"))
      (node (ref "U5") (pin "5") (pinfunction "C2-_5") (pintype "passive"))
    )
    (net (code "81") (name "Net-(U5-V+)") (class "Default")
      (node (ref "C19") (pin "2") (pinfunction "2_2") (pintype "passive"))
      (node (ref "U5") (pin "2") (pinfunction "V+_2") (pintype "power_in"))
    )
    (net (code "82") (name "Net-(U5-V-)") (class "Default")
      (node (ref "C20") (pin "1") (pinfunction "1_1") (pintype "passive"))
      (node (ref "U5") (pin "6") (pinfunction "V-_6") (pintype "power_in"))
    )
    (net (code "83") (name "unconnected-(EC4-Pad6)") (class "Default")
      (node (ref "EC4") (pin "6") (pinfunction "6_6") (pintype "passive+no_connect"))
    )
    (net (code "84") (name "unconnected-(J6-Pad1)") (class "Default")
      (node (ref "J6") (pin "1") (pinfunction "1_1") (pintype "passive"))
    )
    (net (code "85") (name "unconnected-(J6-Pad4)") (class "Default")
      (node (ref "J6") (pin "4") (pinfunction "4_4") (pintype "passive"))
    )
    (net (code "86") (name "unconnected-(J6-Pad6)") (class "Default")
      (node (ref "J6") (pin "6") (pinfunction "6_6") (pintype "passive"))
    )
    (net (code "87") (name "unconnected-(J6-Pad7)") (class "Default")
      (node (ref "J6") (pin "7") (pinfunction "7_7") (pintype "passive"))
    )
    (net (code "88") (name "unconnected-(J6-Pad8)") (class "Default")
      (node (ref "J6") (pin "8") (pinfunction "8_8") (pintype "passive"))
    )
    (net (code "89") (name "unconnected-(J6-Pad9)") (class "Default")
      (node (ref "J6") (pin "9") (pinfunction "9_9") (pintype "passive"))
    )
    (net (code "90") (name "unconnected-(U1A-PA2-Pad12)") (class "Default")
      (node (ref "U1") (pin "12") (pinfunction "PA2_12") (pintype "bidirectional"))
    )
    (net (code "91") (name "unconnected-(U1A-PA3-Pad13)") (class "Default")
      (node (ref "U1") (pin "13") (pinfunction "PA3_13") (pintype "bidirectional"))
    )
    (net (code "92") (name "unconnected-(U1A-PA4-Pad14)") (class "Default")
      (node (ref "U1") (pin "14") (pinfunction "PA4_14") (pintype "bidirectional"))
    )
    (net (code "93") (name "unconnected-(U1A-PA7-Pad17)") (class "Default")
      (node (ref "U1") (pin "17") (pinfunction "PA7_17") (pintype "bidirectional"))
    )
    (net (code "94") (name "unconnected-(U1A-PA9-Pad30)") (class "Default")
      (node (ref "U1") (pin "30") (pinfunction "PA9_30") (pintype "bidirectional"))
    )
    (net (code "95") (name "unconnected-(U1A-PA10-Pad31)") (class "Default")
      (node (ref "U1") (pin "31") (pinfunction "PA10_31") (pintype "bidirectional"))
    )
    (net (code "96") (name "unconnected-(U1A-PF1-OSC_OUT(PF1)-Pad6)") (class "Default")
      (node (ref "U1") (pin "6") (pinfunction "PF1-OSC_OUT(PF1)_6") (pintype "bidirectional+no_connect"))
    )
    (net (code "97") (name "unconnected-(U4-A0-Pad1)") (class "Default")
      (node (ref "U4") (pin "1") (pinfunction "A0_1") (pintype "input+no_connect"))
    )
    (net (code "98") (name "unconnected-(U4-A1-Pad2)") (class "Default")
      (node (ref "U4") (pin "2") (pinfunction "A1_2") (pintype "input+no_connect"))
    )
    (net (code "99") (name "unconnected-(U4-A2-Pad3)") (class "Default")
      (node (ref "U4") (pin "3") (pinfunction "A2_3") (pintype "input+no_connect"))
    )
  )
)
